# AC_mixer_v2.net
KiCad netlist of a schematic drawn in EAGLE
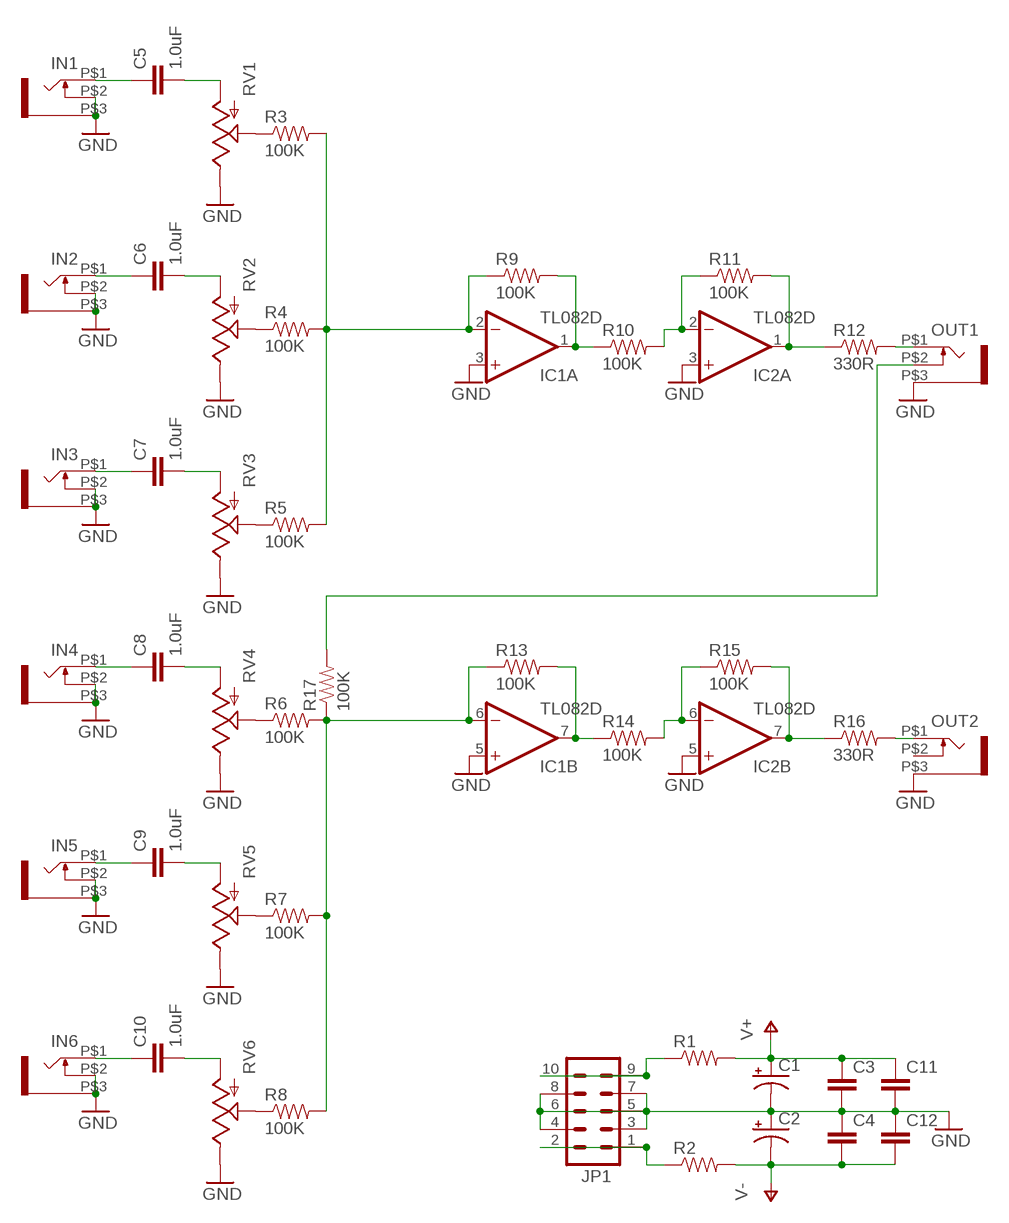
[diagram p0: schematic, sheet 1]

(export (version "E")
  (design (tool "Eeschema 10.0.6"))
  (components
    (comp (ref "C1")
      (value "CAP_POLC")
      (footprint "eagle-import:PANASONIC_C")
      (libsource (lib "eagle-import") (part "CAP_POLC"))
    )
    (comp (ref "C2")
      (value "CAP_POLC")
      (footprint "eagle-import:PANASONIC_C")
      (libsource (lib "eagle-import") (part "CAP_POLC"))
    )
    (comp (ref "C3")
      (value "CAP0805")
      (footprint "eagle-import:0805")
      (libsource (lib "eagle-import") (part "CAP0805"))
    )
    (comp (ref "C4")
      (value "CAP0805")
      (footprint "eagle-import:0805")
      (libsource (lib "eagle-import") (part "CAP0805"))
    )
    (comp (ref "C5")
      (value "1.0uF")
      (footprint "eagle-import:1206")
      (libsource (lib "eagle-import") (part "1.0UF50V10%(1206)"))
    )
    (comp (ref "C6")
      (value "1.0uF")
      (footprint "eagle-import:1206")
      (libsource (lib "eagle-import") (part "1.0UF50V10%(1206)"))
    )
    (comp (ref "C7")
      (value "1.0uF")
      (footprint "eagle-import:1206")
      (libsource (lib "eagle-import") (part "1.0UF50V10%(1206)"))
    )
    (comp (ref "C8")
      (value "1.0uF")
      (footprint "eagle-import:1206")
      (libsource (lib "eagle-import") (part "1.0UF50V10%(1206)"))
    )
    (comp (ref "C9")
      (value "1.0uF")
      (footprint "eagle-import:1206")
      (libsource (lib "eagle-import") (part "1.0UF50V10%(1206)"))
    )
    (comp (ref "C10")
      (value "1.0uF")
      (footprint "eagle-import:1206")
      (libsource (lib "eagle-import") (part "1.0UF50V10%(1206)"))
    )
    (comp (ref "C11")
      (value "CAP0805")
      (footprint "eagle-import:0805")
      (libsource (lib "eagle-import") (part "CAP0805"))
    )
    (comp (ref "C12")
      (value "CAP0805")
      (footprint "eagle-import:0805")
      (libsource (lib "eagle-import") (part "CAP0805"))
    )
    (comp (ref "IC1")
      (value "TL082D")
      (footprint "eagle-import:SO08")
      (libsource (lib "eagle-import") (part "TL082D"))
    )
    (comp (ref "IC2")
      (value "TL082D")
      (footprint "eagle-import:SO08")
      (libsource (lib "eagle-import") (part "TL082D"))
    )
    (comp (ref "IN1")
      (value "WQP-PJ301M-12_JACK")
      (footprint "eagle-import:WQP-PJ301M-12_JACK")
      (libsource (lib "eagle-import") (part "WQP-PJ301M-12_JACK"))
    )
    (comp (ref "IN2")
      (value "WQP-PJ301M-12_JACK")
      (footprint "eagle-import:WQP-PJ301M-12_JACK")
      (libsource (lib "eagle-import") (part "WQP-PJ301M-12_JACK"))
    )
    (comp (ref "IN3")
      (value "WQP-PJ301M-12_JACK")
      (footprint "eagle-import:WQP-PJ301M-12_JACK")
      (libsource (lib "eagle-import") (part "WQP-PJ301M-12_JACK"))
    )
    (comp (ref "IN4")
      (value "WQP-PJ301M-12_JACK")
      (footprint "eagle-import:WQP-PJ301M-12_JACK")
      (libsource (lib "eagle-import") (part "WQP-PJ301M-12_JACK"))
    )
    (comp (ref "IN5")
      (value "WQP-PJ301M-12_JACK")
      (footprint "eagle-import:WQP-PJ301M-12_JACK")
      (libsource (lib "eagle-import") (part "WQP-PJ301M-12_JACK"))
    )
    (comp (ref "IN6")
      (value "WQP-PJ301M-12_JACK")
      (footprint "eagle-import:WQP-PJ301M-12_JACK")
      (libsource (lib "eagle-import") (part "WQP-PJ301M-12_JACK"))
    )
    (comp (ref "JP1")
      (value "M05X2PTH")
      (footprint "eagle-import:AVR_ICSP")
      (libsource (lib "eagle-import") (part "M05X2PTH"))
    )
    (comp (ref "OUT1")
      (value "WQP-PJ301M-12_JACK")
      (footprint "eagle-import:WQP-PJ301M-12_JACK")
      (libsource (lib "eagle-import") (part "WQP-PJ301M-12_JACK"))
    )
    (comp (ref "OUT2")
      (value "WQP-PJ301M-12_JACK")
      (footprint "eagle-import:WQP-PJ301M-12_JACK")
      (libsource (lib "eagle-import") (part "WQP-PJ301M-12_JACK"))
    )
    (comp (ref "R1")
      (value "RESISTOR0805-RES")
      (footprint "eagle-import:0805")
      (libsource (lib "eagle-import") (part "SparkFun-Resistors_RESISTOR0805-RES"))
    )
    (comp (ref "R2")
      (value "RESISTOR0805-RES")
      (footprint "eagle-import:0805")
      (libsource (lib "eagle-import") (part "SparkFun-Resistors_RESISTOR0805-RES"))
    )
    (comp (ref "R3")
      (value "100K")
      (footprint "eagle-import:0805")
      (libsource (lib "eagle-import") (part "RESISTOR0805-RES"))
    )
    (comp (ref "R4")
      (value "100K")
      (footprint "eagle-import:0805")
      (libsource (lib "eagle-import") (part "RESISTOR0805-RES"))
    )
    (comp (ref "R5")
      (value "100K")
      (footprint "eagle-import:0805")
      (libsource (lib "eagle-import") (part "RESISTOR0805-RES"))
    )
    (comp (ref "R6")
      (value "100K")
      (footprint "eagle-import:0805")
      (libsource (lib "eagle-import") (part "RESISTOR0805-RES"))
    )
    (comp (ref "R7")
      (value "100K")
      (footprint "eagle-import:0805")
      (libsource (lib "eagle-import") (part "RESISTOR0805-RES"))
    )
    (comp (ref "R8")
      (value "100K")
      (footprint "eagle-import:0805")
      (libsource (lib "eagle-import") (part "RESISTOR0805-RES"))
    )
    (comp (ref "R9")
      (value "100K")
      (footprint "eagle-import:0805")
      (libsource (lib "eagle-import") (part "RESISTOR0805-RES"))
    )
    (comp (ref "R10")
      (value "100K")
      (footprint "eagle-import:0805")
      (libsource (lib "eagle-import") (part "RESISTOR0805-RES"))
    )
    (comp (ref "R11")
      (value "100K")
      (footprint "eagle-import:0805")
      (libsource (lib "eagle-import") (part "RESISTOR0805-RES"))
    )
    (comp (ref "R12")
      (value "330R")
      (footprint "eagle-import:0805")
      (libsource (lib "eagle-import") (part "RESISTOR0805-RES"))
    )
    (comp (ref "R13")
      (value "100K")
      (footprint "eagle-import:0805")
      (libsource (lib "eagle-import") (part "RESISTOR0805-RES"))
    )
    (comp (ref "R14")
      (value "100K")
      (footprint "eagle-import:0805")
      (libsource (lib "eagle-import") (part "RESISTOR0805-RES"))
    )
    (comp (ref "R15")
      (value "100K")
      (footprint "eagle-import:0805")
      (libsource (lib "eagle-import") (part "RESISTOR0805-RES"))
    )
    (comp (ref "R16")
      (value "330R")
      (footprint "eagle-import:0805")
      (libsource (lib "eagle-import") (part "RESISTOR0805-RES"))
    )
    (comp (ref "R17")
      (value "100K")
      (footprint "eagle-import:0805")
      (libsource (lib "eagle-import") (part "RESISTOR0805-RES"))
    )
    (comp (ref "RV1")
      (value "POT")
      (footprint "eagle-import:ALPS_POT")
      (libsource (lib "eagle-import") (part "POT"))
    )
    (comp (ref "RV2")
      (value "POT")
      (footprint "eagle-import:ALPS_POT")
      (libsource (lib "eagle-import") (part "POT"))
    )
    (comp (ref "RV3")
      (value "POT")
      (footprint "eagle-import:ALPS_POT")
      (libsource (lib "eagle-import") (part "POT"))
    )
    (comp (ref "RV4")
      (value "POT")
      (footprint "eagle-import:ALPS_POT")
      (libsource (lib "eagle-import") (part "POT"))
    )
    (comp (ref "RV5")
      (value "POT")
      (footprint "eagle-import:ALPS_POT")
      (libsource (lib "eagle-import") (part "POT"))
    )
    (comp (ref "RV6")
      (value "POT")
      (footprint "eagle-import:ALPS_POT")
      (libsource (lib "eagle-import") (part "POT"))
    )
  )
  (nets
    (net (code "1") (name "GND") (class "Default")
      (node (ref "C1") (pin "-") (pinfunction "-_-") (pintype "passive"))
      (node (ref "C11") (pin "2") (pinfunction "2_2") (pintype "passive"))
      (node (ref "C12") (pin "1") (pinfunction "1_1") (pintype "passive"))
      (node (ref "C2") (pin "+") (pinfunction "+_+") (pintype "passive"))
      (node (ref "C3") (pin "2") (pinfunction "2_2") (pintype "passive"))
      (node (ref "C4") (pin "1") (pinfunction "1_1") (pintype "passive"))
      (node (ref "IC1") (pin "3") (pinfunction "+IN_3") (pintype "input"))
      (node (ref "IC1") (pin "5") (pinfunction "+IN_5") (pintype "input"))
      (node (ref "IC2") (pin "3") (pinfunction "+IN_3") (pintype "input"))
      (node (ref "IC2") (pin "5") (pinfunction "+IN_5") (pintype "input"))
      (node (ref "IN1") (pin "P$2") (pinfunction "3_P$2") (pintype "passive"))
      (node (ref "IN1") (pin "P$3") (pinfunction "1_P$3") (pintype "passive"))
      (node (ref "IN2") (pin "P$2") (pinfunction "3_P$2") (pintype "passive"))
      (node (ref "IN2") (pin "P$3") (pinfunction "1_P$3") (pintype "passive"))
      (node (ref "IN3") (pin "P$2") (pinfunction "3_P$2") (pintype "passive"))
      (node (ref "IN3") (pin "P$3") (pinfunction "1_P$3") (pintype "passive"))
      (node (ref "IN4") (pin "P$2") (pinfunction "3_P$2") (pintype "passive"))
      (node (ref "IN4") (pin "P$3") (pinfunction "1_P$3") (pintype "passive"))
      (node (ref "IN5") (pin "P$2") (pinfunction "3_P$2") (pintype "passive"))
      (node (ref "IN5") (pin "P$3") (pinfunction "1_P$3") (pintype "passive"))
      (node (ref "IN6") (pin "P$2") (pinfunction "3_P$2") (pintype "passive"))
      (node (ref "IN6") (pin "P$3") (pinfunction "1_P$3") (pintype "passive"))
      (node (ref "JP1") (pin "3") (pinfunction "3_3") (pintype "passive"))
      (node (ref "JP1") (pin "4") (pinfunction "4_4") (pintype "passive"))
      (node (ref "JP1") (pin "5") (pinfunction "5_5") (pintype "passive"))
      (node (ref "JP1") (pin "6") (pinfunction "6_6") (pintype "passive"))
      (node (ref "JP1") (pin "7") (pinfunction "7_7") (pintype "passive"))
      (node (ref "JP1") (pin "8") (pinfunction "8_8") (pintype "passive"))
      (node (ref "OUT1") (pin "P$3") (pinfunction "1_P$3") (pintype "passive"))
      (node (ref "OUT2") (pin "P$3") (pinfunction "1_P$3") (pintype "passive"))
      (node (ref "RV1") (pin "P$1") (pinfunction "E_P$1") (pintype "passive"))
      (node (ref "RV2") (pin "P$1") (pinfunction "E_P$1") (pintype "passive"))
      (node (ref "RV3") (pin "P$1") (pinfunction "E_P$1") (pintype "passive"))
      (node (ref "RV4") (pin "P$1") (pinfunction "E_P$1") (pintype "passive"))
      (node (ref "RV5") (pin "P$1") (pinfunction "E_P$1") (pintype "passive"))
      (node (ref "RV6") (pin "P$1") (pinfunction "E_P$1") (pintype "passive"))
    )
    (net (code "2") (name "Net-(IC1A--IN)") (class "Default")
      (node (ref "IC1") (pin "2") (pinfunction "-IN_2") (pintype "input"))
      (node (ref "R3") (pin "2") (pinfunction "2_2") (pintype "passive"))
      (node (ref "R4") (pin "2") (pinfunction "2_2") (pintype "passive"))
      (node (ref "R5") (pin "2") (pinfunction "2_2") (pintype "passive"))
      (node (ref "R9") (pin "1") (pinfunction "1_1") (pintype "passive"))
    )
    (net (code "3") (name "Net-(IC1A-OUT)") (class "Default")
      (node (ref "IC1") (pin "1") (pinfunction "OUT_1") (pintype "output"))
      (node (ref "R10") (pin "1") (pinfunction "1_1") (pintype "passive"))
      (node (ref "R9") (pin "2") (pinfunction "2_2") (pintype "passive"))
    )
    (net (code "4") (name "Net-(IC1B--IN)") (class "Default")
      (node (ref "IC1") (pin "6") (pinfunction "-IN_6") (pintype "input"))
      (node (ref "R13") (pin "1") (pinfunction "1_1") (pintype "passive"))
      (node (ref "R17") (pin "1") (pinfunction "1_1") (pintype "passive"))
      (node (ref "R6") (pin "2") (pinfunction "2_2") (pintype "passive"))
      (node (ref "R7") (pin "2") (pinfunction "2_2") (pintype "passive"))
      (node (ref "R8") (pin "2") (pinfunction "2_2") (pintype "passive"))
    )
    (net (code "5") (name "Net-(IC1B-OUT)") (class "Default")
      (node (ref "IC1") (pin "7") (pinfunction "OUT_7") (pintype "output"))
      (node (ref "R13") (pin "2") (pinfunction "2_2") (pintype "passive"))
      (node (ref "R14") (pin "1") (pinfunction "1_1") (pintype "passive"))
    )
    (net (code "6") (name "Net-(IC2A--IN)") (class "Default")
      (node (ref "IC2") (pin "2") (pinfunction "-IN_2") (pintype "input"))
      (node (ref "R10") (pin "2") (pinfunction "2_2") (pintype "passive"))
      (node (ref "R11") (pin "1") (pinfunction "1_1") (pintype "passive"))
    )
    (net (code "7") (name "Net-(IC2A-OUT)") (class "Default")
      (node (ref "IC2") (pin "1") (pinfunction "OUT_1") (pintype "output"))
      (node (ref "R11") (pin "2") (pinfunction "2_2") (pintype "passive"))
      (node (ref "R12") (pin "1") (pinfunction "1_1") (pintype "passive"))
    )
    (net (code "8") (name "Net-(IC2B--IN)") (class "Default")
      (node (ref "IC2") (pin "6") (pinfunction "-IN_6") (pintype "input"))
      (node (ref "R14") (pin "2") (pinfunction "2_2") (pintype "passive"))
      (node (ref "R15") (pin "1") (pinfunction "1_1") (pintype "passive"))
    )
    (net (code "9") (name "Net-(IC2B-OUT)") (class "Default")
      (node (ref "IC2") (pin "7") (pinfunction "OUT_7") (pintype "output"))
      (node (ref "R15") (pin "2") (pinfunction "2_2") (pintype "passive"))
      (node (ref "R16") (pin "1") (pinfunction "1_1") (pintype "passive"))
    )
    (net (code "10") (name "Net-(IN1-2)") (class "Default")
      (node (ref "C5") (pin "1") (pinfunction "1_1") (pintype "passive"))
      (node (ref "IN1") (pin "P$1") (pinfunction "2_P$1") (pintype "passive"))
    )
    (net (code "11") (name "Net-(IN2-2)") (class "Default")
      (node (ref "C6") (pin "1") (pinfunction "1_1") (pintype "passive"))
      (node (ref "IN2") (pin "P$1") (pinfunction "2_P$1") (pintype "passive"))
    )
    (net (code "12") (name "Net-(IN3-2)") (class "Default")
      (node (ref "C7") (pin "1") (pinfunction "1_1") (pintype "passive"))
      (node (ref "IN3") (pin "P$1") (pinfunction "2_P$1") (pintype "passive"))
    )
    (net (code "13") (name "Net-(IN4-2)") (class "Default")
      (node (ref "C8") (pin "1") (pinfunction "1_1") (pintype "passive"))
      (node (ref "IN4") (pin "P$1") (pinfunction "2_P$1") (pintype "passive"))
    )
    (net (code "14") (name "Net-(IN5-2)") (class "Default")
      (node (ref "C9") (pin "1") (pinfunction "1_1") (pintype "passive"))
      (node (ref "IN5") (pin "P$1") (pinfunction "2_P$1") (pintype "passive"))
    )
    (net (code "15") (name "Net-(IN6-2)") (class "Default")
      (node (ref "C10") (pin "1") (pinfunction "1_1") (pintype "passive"))
      (node (ref "IN6") (pin "P$1") (pinfunction "2_P$1") (pintype "passive"))
    )
    (net (code "16") (name "Net-(JP1-Pad1)") (class "Default")
      (node (ref "JP1") (pin "1") (pinfunction "1_1") (pintype "passive"))
      (node (ref "JP1") (pin "2") (pinfunction "2_2") (pintype "passive"))
      (node (ref "R2") (pin "1") (pinfunction "1_1") (pintype "passive"))
    )
    (net (code "17") (name "Net-(JP1-Pad10)") (class "Default")
      (node (ref "JP1") (pin "10") (pinfunction "10_10") (pintype "passive"))
      (node (ref "JP1") (pin "9") (pinfunction "9_9") (pintype "passive"))
      (node (ref "R1") (pin "1") (pinfunction "1_1") (pintype "passive"))
    )
    (net (code "18") (name "Net-(OUT1-2)") (class "Default")
      (node (ref "OUT1") (pin "P$1") (pinfunction "2_P$1") (pintype "passive"))
      (node (ref "R12") (pin "2") (pinfunction "2_2") (pintype "passive"))
    )
    (net (code "19") (name "Net-(OUT1-3)") (class "Default")
      (node (ref "OUT1") (pin "P$2") (pinfunction "3_P$2") (pintype "passive"))
      (node (ref "R17") (pin "2") (pinfunction "2_2") (pintype "passive"))
    )
    (net (code "20") (name "Net-(OUT2-2)") (class "Default")
      (node (ref "OUT2") (pin "P$1") (pinfunction "2_P$1") (pintype "passive"))
      (node (ref "R16") (pin "2") (pinfunction "2_2") (pintype "passive"))
    )
    (net (code "21") (name "Net-(RV1-A)") (class "Default")
      (node (ref "C5") (pin "2") (pinfunction "2_2") (pintype "passive"))
      (node (ref "RV1") (pin "P$3") (pinfunction "A_P$3") (pintype "passive"))
    )
    (net (code "22") (name "Net-(RV1-S)") (class "Default")
      (node (ref "R3") (pin "1") (pinfunction "1_1") (pintype "passive"))
      (node (ref "RV1") (pin "P$2") (pinfunction "S_P$2") (pintype "passive"))
    )
    (net (code "23") (name "Net-(RV2-A)") (class "Default")
      (node (ref "C6") (pin "2") (pinfunction "2_2") (pintype "passive"))
      (node (ref "RV2") (pin "P$3") (pinfunction "A_P$3") (pintype "passive"))
    )
    (net (code "24") (name "Net-(RV2-S)") (class "Default")
      (node (ref "R4") (pin "1") (pinfunction "1_1") (pintype "passive"))
      (node (ref "RV2") (pin "P$2") (pinfunction "S_P$2") (pintype "passive"))
    )
    (net (code "25") (name "Net-(RV3-A)") (class "Default")
      (node (ref "C7") (pin "2") (pinfunction "2_2") (pintype "passive"))
      (node (ref "RV3") (pin "P$3") (pinfunction "A_P$3") (pintype "passive"))
    )
    (net (code "26") (name "Net-(RV3-S)") (class "Default")
      (node (ref "R5") (pin "1") (pinfunction "1_1") (pintype "passive"))
      (node (ref "RV3") (pin "P$2") (pinfunction "S_P$2") (pintype "passive"))
    )
    (net (code "27") (name "Net-(RV4-A)") (class "Default")
      (node (ref "C8") (pin "2") (pinfunction "2_2") (pintype "passive"))
      (node (ref "RV4") (pin "P$3") (pinfunction "A_P$3") (pintype "passive"))
    )
    (net (code "28") (name "Net-(RV4-S)") (class "Default")
      (node (ref "R6") (pin "1") (pinfunction "1_1") (pintype "passive"))
      (node (ref "RV4") (pin "P$2") (pinfunction "S_P$2") (pintype "passive"))
    )
    (net (code "29") (name "Net-(RV5-A)") (class "Default")
      (node (ref "C9") (pin "2") (pinfunction "2_2") (pintype "passive"))
      (node (ref "RV5") (pin "P$3") (pinfunction "A_P$3") (pintype "passive"))
    )
    (net (code "30") (name "Net-(RV5-S)") (class "Default")
      (node (ref "R7") (pin "1") (pinfunction "1_1") (pintype "passive"))
      (node (ref "RV5") (pin "P$2") (pinfunction "S_P$2") (pintype "passive"))
    )
    (net (code "31") (name "Net-(RV6-A)") (class "Default")
      (node (ref "C10") (pin "2") (pinfunction "2_2") (pintype "passive"))
      (node (ref "RV6") (pin "P$3") (pinfunction "A_P$3") (pintype "passive"))
    )
    (net (code "32") (name "Net-(RV6-S)") (class "Default")
      (node (ref "R8") (pin "1") (pinfunction "1_1") (pintype "passive"))
      (node (ref "RV6") (pin "P$2") (pinfunction "S_P$2") (pintype "passive"))
    )
    (net (code "33") (name "V+") (class "Default")
      (node (ref "C1") (pin "+") (pinfunction "+_+") (pintype "passive"))
      (node (ref "C11") (pin "1") (pinfunction "1_1") (pintype "passive"))
      (node (ref "C3") (pin "1") (pinfunction "1_1") (pintype "passive"))
      (node (ref "R1") (pin "2") (pinfunction "2_2") (pintype "passive"))
    )
    (net (code "34") (name "V-") (class "Default")
      (node (ref "C12") (pin "2") (pinfunction "2_2") (pintype "passive"))
      (node (ref "C2") (pin "-") (pinfunction "-_-") (pintype "passive"))
      (node (ref "C4") (pin "2") (pinfunction "2_2") (pintype "passive"))
      (node (ref "R2") (pin "2") (pinfunction "2_2") (pintype "passive"))
    )
    (net (code "35") (name "unconnected-(OUT2-3-PadP$2)") (class "Default")
      (node (ref "OUT2") (pin "P$2") (pinfunction "3_P$2") (pintype "passive"))
    )
  )
)
